# Atrix_adapter.net
KiCad netlist of a schematic drawn in EAGLE
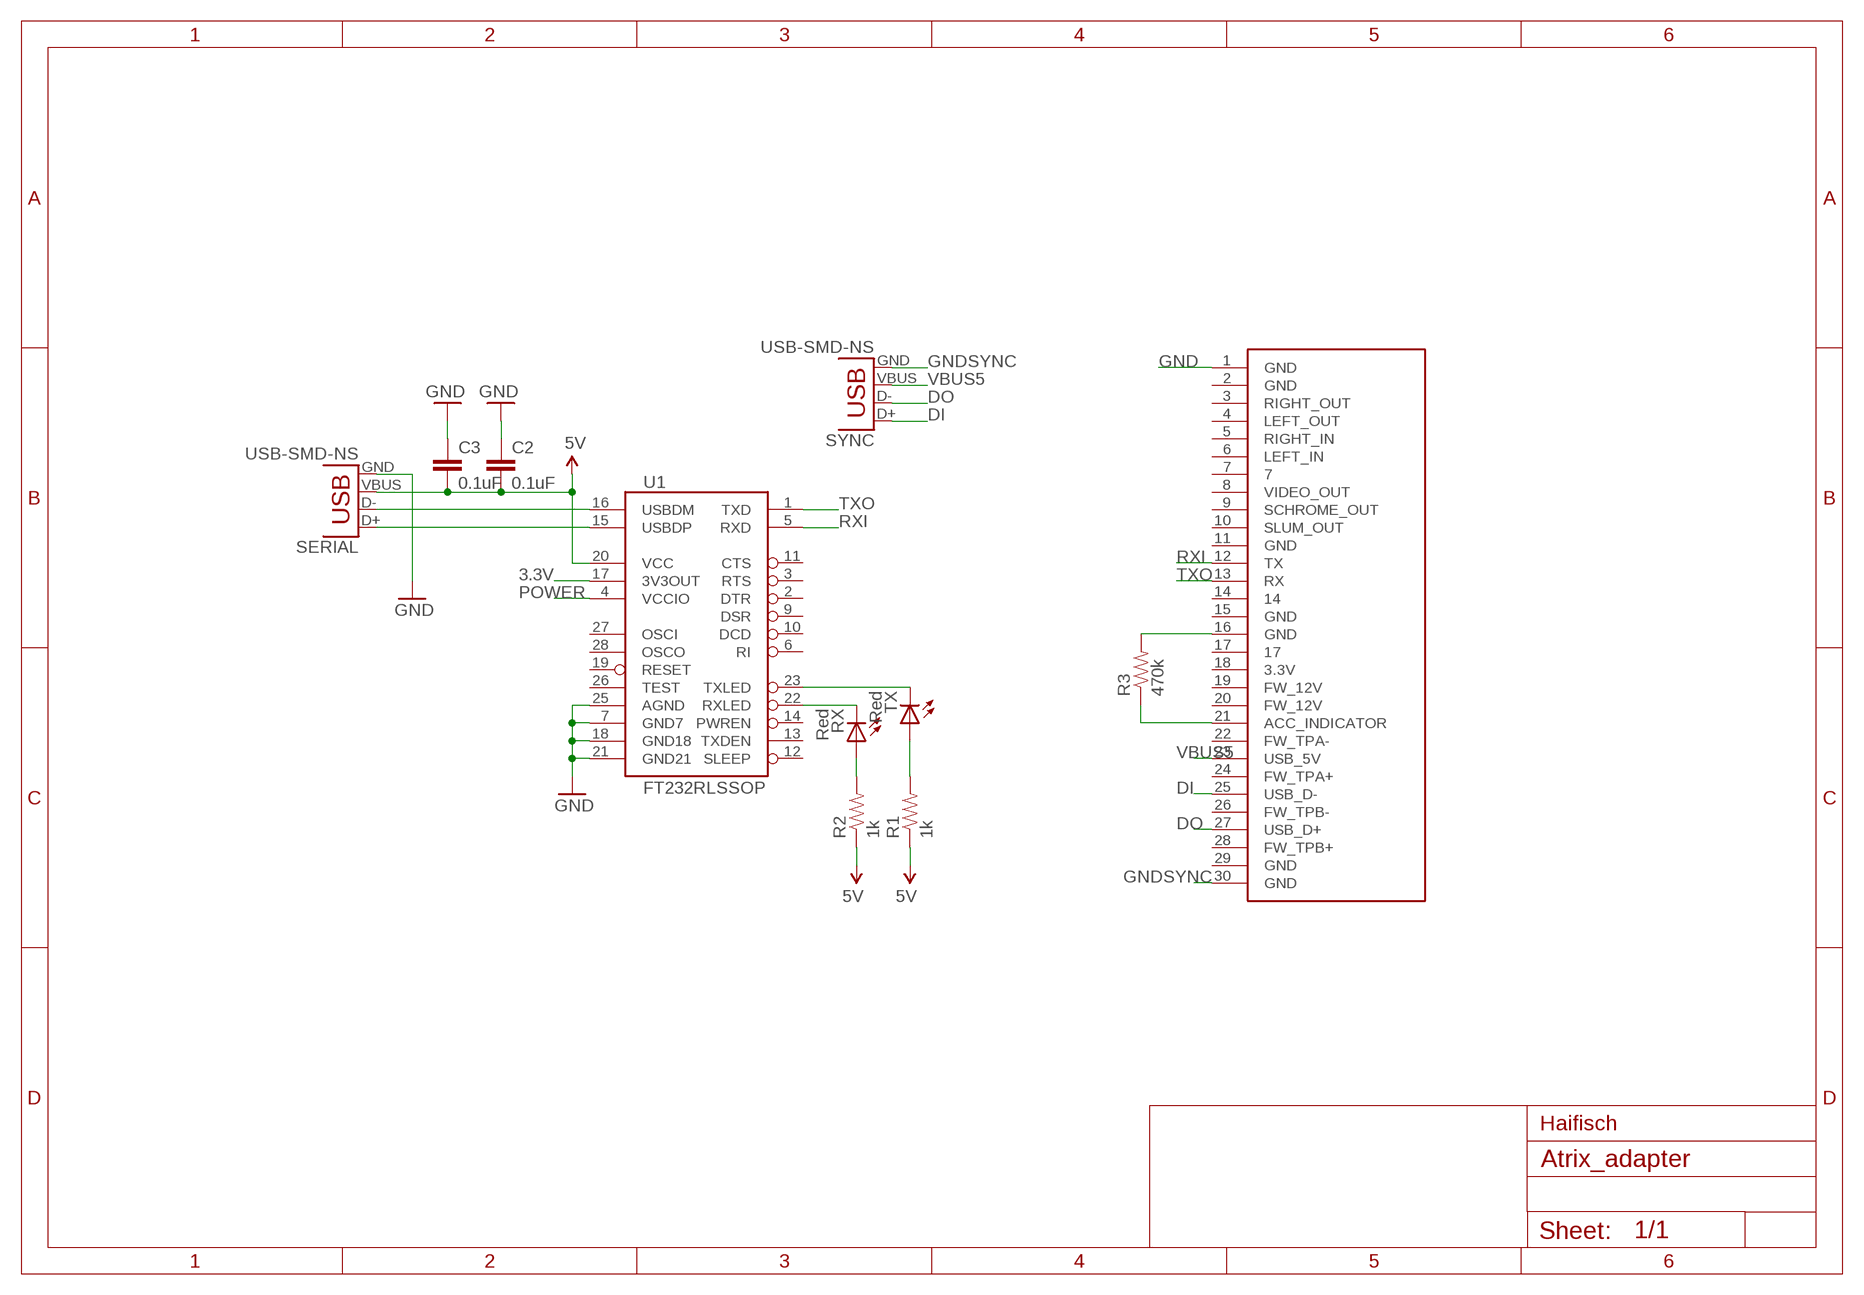
[diagram p0: schematic, sheet 1]

(export (version "E")
  (design (tool "Eeschema 10.0.6"))
  (components
    (comp (ref "C2")
      (value "0.1uF")
      (footprint "eagle-import:0402-CAP")
      (libsource (lib "eagle-import") (part "CAP0402-CAP"))
    )
    (comp (ref "C3")
      (value "0.1uF")
      (footprint "eagle-import:0402-CAP")
      (libsource (lib "eagle-import") (part "CAP0402-CAP"))
    )
    (comp (ref "R1")
      (value "1k")
      (footprint "eagle-import:0402-RES")
      (libsource (lib "eagle-import") (part "RESISTOR0402-RES"))
    )
    (comp (ref "R2")
      (value "1k")
      (footprint "eagle-import:0402-RES")
      (libsource (lib "eagle-import") (part "RESISTOR0402-RES"))
    )
    (comp (ref "R3")
      (value "470k")
      (footprint "eagle-import:0402-RES")
      (libsource (lib "eagle-import") (part "RESISTOR0402-RES"))
    )
    (comp (ref "RX")
      (value "Red")
      (footprint "eagle-import:CHIP-LED0603")
      (libsource (lib "eagle-import") (part "LEDCHIP-LED0603"))
    )
    (comp (ref "SERIAL")
      (value "USB-SMD-NS")
      (footprint "eagle-import:USB-MINIB-NOSTOP")
      (libsource (lib "eagle-import") (part "USB-SMD-NS"))
    )
    (comp (ref "SYNC")
      (value "USB-SMD-NS")
      (footprint "eagle-import:USB-MINIB-NOSTOP")
      (libsource (lib "eagle-import") (part "USB-SMD-NS"))
    )
    (comp (ref "TX")
      (value "Red")
      (footprint "eagle-import:CHIP-LED0603")
      (libsource (lib "eagle-import") (part "LEDCHIP-LED0603"))
    )
    (comp (ref "U$1")
      (value "IPOD_CONNECTOR_MALE")
      (footprint "eagle-import:IPOD_MALE_CONNECTOR")
      (libsource (lib "eagle-import") (part "IPOD_CONNECTOR_MALE"))
    )
    (comp (ref "U1")
      (value "FT232RLSSOP")
      (footprint "eagle-import:SSOP28DB")
      (libsource (lib "eagle-import") (part "FT232RLSSOP"))
    )
  )
  (nets
    (net (code "1") (name "/3.3V") (class "Default")
      (node (ref "U1") (pin "17") (pinfunction "3V3OUT_17") (pintype "output"))
    )
    (net (code "2") (name "/DI") (class "Default")
      (node (ref "SYNC") (pin "D+") (pinfunction "D+_D+") (pintype "bidirectional"))
      (node (ref "U$1") (pin "25") (pinfunction "USB_D-_25") (pintype "bidirectional"))
    )
    (net (code "3") (name "/DO") (class "Default")
      (node (ref "SYNC") (pin "D-") (pinfunction "D-_D-") (pintype "bidirectional"))
      (node (ref "U$1") (pin "27") (pinfunction "USB_D+_27") (pintype "bidirectional"))
    )
    (net (code "4") (name "/GNDSYNC") (class "Default")
      (node (ref "SYNC") (pin "GND") (pinfunction "GND_GND") (pintype "bidirectional"))
      (node (ref "U$1") (pin "30") (pinfunction "GND_30") (pintype "bidirectional"))
    )
    (net (code "5") (name "/POWER") (class "Default")
      (node (ref "U1") (pin "4") (pinfunction "VCCIO_4") (pintype "power_in"))
    )
    (net (code "6") (name "/RXI") (class "Default")
      (node (ref "U$1") (pin "12") (pinfunction "TX_12") (pintype "bidirectional"))
      (node (ref "U1") (pin "5") (pinfunction "RXD_5") (pintype "input"))
    )
    (net (code "7") (name "/TXO") (class "Default")
      (node (ref "U$1") (pin "13") (pinfunction "RX_13") (pintype "bidirectional"))
      (node (ref "U1") (pin "1") (pinfunction "TXD_1") (pintype "output"))
    )
    (net (code "8") (name "/VBUS5") (class "Default")
      (node (ref "SYNC") (pin "VBUS") (pinfunction "VBUS_VBUS") (pintype "bidirectional"))
      (node (ref "U$1") (pin "23") (pinfunction "USB_5V_23") (pintype "bidirectional"))
    )
    (net (code "9") (name "5V") (class "Default")
      (node (ref "C2") (pin "2") (pinfunction "2_2") (pintype "passive"))
      (node (ref "C3") (pin "2") (pinfunction "2_2") (pintype "passive"))
      (node (ref "R1") (pin "1") (pinfunction "1_1") (pintype "passive"))
      (node (ref "R2") (pin "1") (pinfunction "1_1") (pintype "passive"))
      (node (ref "SERIAL") (pin "VBUS") (pinfunction "VBUS_VBUS") (pintype "bidirectional"))
      (node (ref "U1") (pin "20") (pinfunction "VCC_20") (pintype "power_in"))
    )
    (net (code "10") (name "GND") (class "Default")
      (node (ref "C2") (pin "1") (pinfunction "1_1") (pintype "passive"))
      (node (ref "C3") (pin "1") (pinfunction "1_1") (pintype "passive"))
      (node (ref "SERIAL") (pin "GND") (pinfunction "GND_GND") (pintype "bidirectional"))
      (node (ref "U$1") (pin "1") (pinfunction "GND_1") (pintype "bidirectional"))
      (node (ref "U1") (pin "18") (pinfunction "GND18_18") (pintype "power_in"))
      (node (ref "U1") (pin "21") (pinfunction "GND21_21") (pintype "power_in"))
      (node (ref "U1") (pin "25") (pinfunction "AGND_25") (pintype "power_in"))
      (node (ref "U1") (pin "7") (pinfunction "GND7_7") (pintype "power_in"))
    )
    (net (code "11") (name "Net-(R1-Pad2)") (class "Default")
      (node (ref "R1") (pin "2") (pinfunction "2_2") (pintype "passive"))
      (node (ref "TX") (pin "A") (pinfunction "A_A") (pintype "passive"))
    )
    (net (code "12") (name "Net-(R2-Pad2)") (class "Default")
      (node (ref "R2") (pin "2") (pinfunction "2_2") (pintype "passive"))
      (node (ref "RX") (pin "A") (pinfunction "A_A") (pintype "passive"))
    )
    (net (code "13") (name "Net-(R3-Pad2)") (class "Default")
      (node (ref "R3") (pin "2") (pinfunction "2_2") (pintype "passive"))
      (node (ref "U$1") (pin "16") (pinfunction "GND_16") (pintype "bidirectional"))
    )
    (net (code "14") (name "Net-(U$1-ACC_INDICATOR)") (class "Default")
      (node (ref "R3") (pin "1") (pinfunction "1_1") (pintype "passive"))
      (node (ref "U$1") (pin "21") (pinfunction "ACC_INDICATOR_21") (pintype "bidirectional"))
    )
    (net (code "15") (name "Net-(U1-RXLED)") (class "Default")
      (node (ref "RX") (pin "C") (pinfunction "C_C") (pintype "passive"))
      (node (ref "U1") (pin "22") (pinfunction "RXLED_22") (pintype "input"))
    )
    (net (code "16") (name "Net-(U1-TXLED)") (class "Default")
      (node (ref "TX") (pin "C") (pinfunction "C_C") (pintype "passive"))
      (node (ref "U1") (pin "23") (pinfunction "TXLED_23") (pintype "input"))
    )
    (net (code "17") (name "Net-(U1-USBDM)") (class "Default")
      (node (ref "SERIAL") (pin "D-") (pinfunction "D-_D-") (pintype "bidirectional"))
      (node (ref "U1") (pin "16") (pinfunction "USBDM_16") (pintype "bidirectional"))
    )
    (net (code "18") (name "Net-(U1-USBDP)") (class "Default")
      (node (ref "SERIAL") (pin "D+") (pinfunction "D+_D+") (pintype "bidirectional"))
      (node (ref "U1") (pin "15") (pinfunction "USBDP_15") (pintype "bidirectional"))
    )
    (net (code "19") (name "unconnected-(U$1-3.3V-Pad18)") (class "Default")
      (node (ref "U$1") (pin "18") (pinfunction "3.3V_18") (pintype "bidirectional"))
    )
    (net (code "20") (name "unconnected-(U$1-FW_12V-Pad19)") (class "Default")
      (node (ref "U$1") (pin "19") (pinfunction "FW_12V_19") (pintype "bidirectional"))
    )
    (net (code "21") (name "unconnected-(U$1-FW_12V-Pad20)") (class "Default")
      (node (ref "U$1") (pin "20") (pinfunction "FW_12V_20") (pintype "bidirectional"))
    )
    (net (code "22") (name "unconnected-(U$1-FW_TPA+-Pad24)") (class "Default")
      (node (ref "U$1") (pin "24") (pinfunction "FW_TPA+_24") (pintype "bidirectional"))
    )
    (net (code "23") (name "unconnected-(U$1-FW_TPA--Pad22)") (class "Default")
      (node (ref "U$1") (pin "22") (pinfunction "FW_TPA-_22") (pintype "bidirectional"))
    )
    (net (code "24") (name "unconnected-(U$1-FW_TPB+-Pad28)") (class "Default")
      (node (ref "U$1") (pin "28") (pinfunction "FW_TPB+_28") (pintype "bidirectional"))
    )
    (net (code "25") (name "unconnected-(U$1-FW_TPB--Pad26)") (class "Default")
      (node (ref "U$1") (pin "26") (pinfunction "FW_TPB-_26") (pintype "bidirectional"))
    )
    (net (code "26") (name "unconnected-(U$1-GND-Pad2)") (class "Default")
      (node (ref "U$1") (pin "2") (pinfunction "GND_2") (pintype "bidirectional"))
    )
    (net (code "27") (name "unconnected-(U$1-GND-Pad11)") (class "Default")
      (node (ref "U$1") (pin "11") (pinfunction "GND_11") (pintype "bidirectional"))
    )
    (net (code "28") (name "unconnected-(U$1-GND-Pad15)") (class "Default")
      (node (ref "U$1") (pin "15") (pinfunction "GND_15") (pintype "bidirectional"))
    )
    (net (code "29") (name "unconnected-(U$1-GND-Pad29)") (class "Default")
      (node (ref "U$1") (pin "29") (pinfunction "GND_29") (pintype "bidirectional"))
    )
    (net (code "30") (name "unconnected-(U$1-LEFT_IN-Pad6)") (class "Default")
      (node (ref "U$1") (pin "6") (pinfunction "LEFT_IN_6") (pintype "bidirectional"))
    )
    (net (code "31") (name "unconnected-(U$1-LEFT_OUT-Pad4)") (class "Default")
      (node (ref "U$1") (pin "4") (pinfunction "LEFT_OUT_4") (pintype "bidirectional"))
    )
    (net (code "32") (name "unconnected-(U$1-Pad7)") (class "Default")
      (node (ref "U$1") (pin "7") (pinfunction "7_7") (pintype "bidirectional"))
    )
    (net (code "33") (name "unconnected-(U$1-Pad14)") (class "Default")
      (node (ref "U$1") (pin "14") (pinfunction "14_14") (pintype "bidirectional"))
    )
    (net (code "34") (name "unconnected-(U$1-Pad17)") (class "Default")
      (node (ref "U$1") (pin "17") (pinfunction "17_17") (pintype "bidirectional"))
    )
    (net (code "35") (name "unconnected-(U$1-RIGHT_IN-Pad5)") (class "Default")
      (node (ref "U$1") (pin "5") (pinfunction "RIGHT_IN_5") (pintype "bidirectional"))
    )
    (net (code "36") (name "unconnected-(U$1-RIGHT_OUT-Pad3)") (class "Default")
      (node (ref "U$1") (pin "3") (pinfunction "RIGHT_OUT_3") (pintype "bidirectional"))
    )
    (net (code "37") (name "unconnected-(U$1-SCHROME_OUT-Pad9)") (class "Default")
      (node (ref "U$1") (pin "9") (pinfunction "SCHROME_OUT_9") (pintype "bidirectional"))
    )
    (net (code "38") (name "unconnected-(U$1-SLUM_OUT-Pad10)") (class "Default")
      (node (ref "U$1") (pin "10") (pinfunction "SLUM_OUT_10") (pintype "bidirectional"))
    )
    (net (code "39") (name "unconnected-(U$1-VIDEO_OUT-Pad8)") (class "Default")
      (node (ref "U$1") (pin "8") (pinfunction "VIDEO_OUT_8") (pintype "bidirectional"))
    )
    (net (code "40") (name "unconnected-(U1-CTS-Pad11)") (class "Default")
      (node (ref "U1") (pin "11") (pinfunction "CTS_11") (pintype "input"))
    )
    (net (code "41") (name "unconnected-(U1-DCD-Pad10)") (class "Default")
      (node (ref "U1") (pin "10") (pinfunction "DCD_10") (pintype "input"))
    )
    (net (code "42") (name "unconnected-(U1-DSR-Pad9)") (class "Default")
      (node (ref "U1") (pin "9") (pinfunction "DSR_9") (pintype "input"))
    )
    (net (code "43") (name "unconnected-(U1-DTR-Pad2)") (class "Default")
      (node (ref "U1") (pin "2") (pinfunction "DTR_2") (pintype "output"))
    )
    (net (code "44") (name "unconnected-(U1-OSCI-Pad27)") (class "Default")
      (node (ref "U1") (pin "27") (pinfunction "OSCI_27") (pintype "input"))
    )
    (net (code "45") (name "unconnected-(U1-OSCO-Pad28)") (class "Default")
      (node (ref "U1") (pin "28") (pinfunction "OSCO_28") (pintype "output"))
    )
    (net (code "46") (name "unconnected-(U1-PWREN-Pad14)") (class "Default")
      (node (ref "U1") (pin "14") (pinfunction "PWREN_14") (pintype "input"))
    )
    (net (code "47") (name "unconnected-(U1-RESET-Pad19)") (class "Default")
      (node (ref "U1") (pin "19") (pinfunction "RESET_19") (pintype "input"))
    )
    (net (code "48") (name "unconnected-(U1-RI-Pad6)") (class "Default")
      (node (ref "U1") (pin "6") (pinfunction "RI_6") (pintype "input"))
    )
    (net (code "49") (name "unconnected-(U1-RTS-Pad3)") (class "Default")
      (node (ref "U1") (pin "3") (pinfunction "RTS_3") (pintype "output"))
    )
    (net (code "50") (name "unconnected-(U1-SLEEP-Pad12)") (class "Default")
      (node (ref "U1") (pin "12") (pinfunction "SLEEP_12") (pintype "input"))
    )
    (net (code "51") (name "unconnected-(U1-TEST-Pad26)") (class "Default")
      (node (ref "U1") (pin "26") (pinfunction "TEST_26") (pintype "input"))
    )
    (net (code "52") (name "unconnected-(U1-TXDEN-Pad13)") (class "Default")
      (node (ref "U1") (pin "13") (pinfunction "TXDEN_13") (pintype "input"))
    )
  )
)
